# cv05dobes.net
KiCad netlist of a schematic drawn in EAGLE
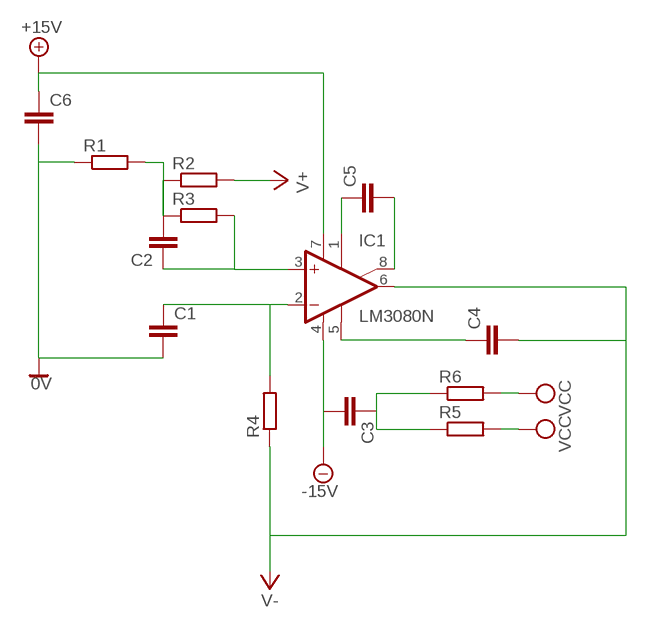
[diagram p0: schematic, sheet 1]

(export (version "E")
  (design (tool "Eeschema 10.0.6"))
  (components
    (comp (ref "C1")
      (value "C-EU075-042X103")
      (footprint "eagle-import:C075-042X103")
      (libsource (lib "eagle-import") (part "C-EU075-042X103"))
    )
    (comp (ref "C2")
      (value "C-EU075-042X103")
      (footprint "eagle-import:C075-042X103")
      (libsource (lib "eagle-import") (part "C-EU075-042X103"))
    )
    (comp (ref "C3")
      (value "C-EU075-052X106")
      (footprint "eagle-import:C075-052X106")
      (libsource (lib "eagle-import") (part "C-EU075-052X106"))
    )
    (comp (ref "C4")
      (value "C-EU075-052X106")
      (footprint "eagle-import:C075-052X106")
      (libsource (lib "eagle-import") (part "C-EU075-052X106"))
    )
    (comp (ref "C5")
      (value "C-EU050-030X075")
      (footprint "eagle-import:C050-030X075")
      (libsource (lib "eagle-import") (part "C-EU050-030X075"))
    )
    (comp (ref "C6")
      (value "C-EU050-030X075")
      (footprint "eagle-import:C050-030X075")
      (libsource (lib "eagle-import") (part "C-EU050-030X075"))
    )
    (comp (ref "IC1")
      (value "LM3080N")
      (footprint "eagle-import:DIL08")
      (libsource (lib "eagle-import") (part "3080NLM"))
    )
    (comp (ref "R1")
      (value "R-EU_0613/15")
      (footprint "eagle-import:P0613_15")
      (libsource (lib "eagle-import") (part "R-EU_0613/15"))
    )
    (comp (ref "R2")
      (value "R-EU_0613/15")
      (footprint "eagle-import:P0613_15")
      (libsource (lib "eagle-import") (part "R-EU_0613/15"))
    )
    (comp (ref "R3")
      (value "R-EU_0613/15")
      (footprint "eagle-import:P0613_15")
      (libsource (lib "eagle-import") (part "R-EU_0613/15"))
    )
    (comp (ref "R4")
      (value "R-EU_0613/15")
      (footprint "eagle-import:P0613_15")
      (libsource (lib "eagle-import") (part "R-EU_0613/15"))
    )
    (comp (ref "R5")
      (value "R-EU_0414/15")
      (footprint "eagle-import:0414_15")
      (libsource (lib "eagle-import") (part "R-EU_0414/15"))
    )
    (comp (ref "R6")
      (value "R-EU_0414/15")
      (footprint "eagle-import:0414_15")
      (libsource (lib "eagle-import") (part "R-EU_0414/15"))
    )
  )
  (nets
    (net (code "1") (name "+15V") (class "Default")
      (node (ref "C6") (pin "1") (pinfunction "1_1") (pintype "passive"))
      (node (ref "IC1") (pin "7") (pinfunction "V+_7") (pintype "power_in"))
    )
    (net (code "2") (name "-15V") (class "Default")
      (node (ref "C3") (pin "2") (pinfunction "2_2") (pintype "passive"))
      (node (ref "IC1") (pin "4") (pinfunction "V-_4") (pintype "power_in"))
    )
    (net (code "3") (name "0V") (class "Default")
      (node (ref "C1") (pin "2") (pinfunction "2_2") (pintype "passive"))
      (node (ref "C6") (pin "2") (pinfunction "2_2") (pintype "passive"))
      (node (ref "R1") (pin "1") (pinfunction "1_1") (pintype "passive"))
    )
    (net (code "4") (name "Net-(C2-Pad2)") (class "Default")
      (node (ref "C2") (pin "2") (pinfunction "2_2") (pintype "passive"))
      (node (ref "R1") (pin "2") (pinfunction "2_2") (pintype "passive"))
      (node (ref "R2") (pin "1") (pinfunction "1_1") (pintype "passive"))
      (node (ref "R3") (pin "1") (pinfunction "1_1") (pintype "passive"))
    )
    (net (code "5") (name "Net-(IC1-+IN)") (class "Default")
      (node (ref "C2") (pin "1") (pinfunction "1_1") (pintype "passive"))
      (node (ref "IC1") (pin "3") (pinfunction "+IN_3") (pintype "input"))
      (node (ref "R3") (pin "2") (pinfunction "2_2") (pintype "passive"))
    )
    (net (code "6") (name "Net-(IC1--IN)") (class "Default")
      (node (ref "C1") (pin "1") (pinfunction "1_1") (pintype "passive"))
      (node (ref "IC1") (pin "2") (pinfunction "-IN_2") (pintype "input"))
      (node (ref "R4") (pin "2") (pinfunction "2_2") (pintype "passive"))
    )
    (net (code "7") (name "Net-(IC1-ON1)") (class "Default")
      (node (ref "C5") (pin "1") (pinfunction "1_1") (pintype "passive"))
      (node (ref "IC1") (pin "1") (pinfunction "ON1_1") (pintype "passive"))
    )
    (net (code "8") (name "Net-(IC1-ON2)") (class "Default")
      (node (ref "C5") (pin "2") (pinfunction "2_2") (pintype "passive"))
      (node (ref "IC1") (pin "8") (pinfunction "ON2_8") (pintype "passive"))
    )
    (net (code "9") (name "Net-(IC1-OPT)") (class "Default")
      (node (ref "C4") (pin "1") (pinfunction "1_1") (pintype "passive"))
      (node (ref "IC1") (pin "5") (pinfunction "OPT_5") (pintype "passive"))
    )
    (net (code "10") (name "Net-(R5-Pad1)") (class "Default")
      (node (ref "R5") (pin "1") (pinfunction "1_1") (pintype "passive"))
      (node (ref "R6") (pin "1") (pinfunction "1_1") (pintype "passive"))
    )
    (net (code "11") (name "V+") (class "Default")
      (node (ref "R2") (pin "2") (pinfunction "2_2") (pintype "passive"))
    )
    (net (code "12") (name "V-") (class "Default")
      (node (ref "C4") (pin "2") (pinfunction "2_2") (pintype "passive"))
      (node (ref "IC1") (pin "6") (pinfunction "OUT_6") (pintype "output"))
      (node (ref "R4") (pin "1") (pinfunction "1_1") (pintype "passive"))
    )
    (net (code "13") (name "VCC") (class "Default")
      (node (ref "R5") (pin "2") (pinfunction "2_2") (pintype "passive"))
      (node (ref "R6") (pin "2") (pinfunction "2_2") (pintype "passive"))
    )
    (net (code "14") (name "unconnected-(C3-Pad1)") (class "Default")
      (node (ref "C3") (pin "1") (pinfunction "1_1") (pintype "passive"))
    )
  )
)
